# BCM_ECU.net
KiCad netlist of a schematic drawn in Altium Designer
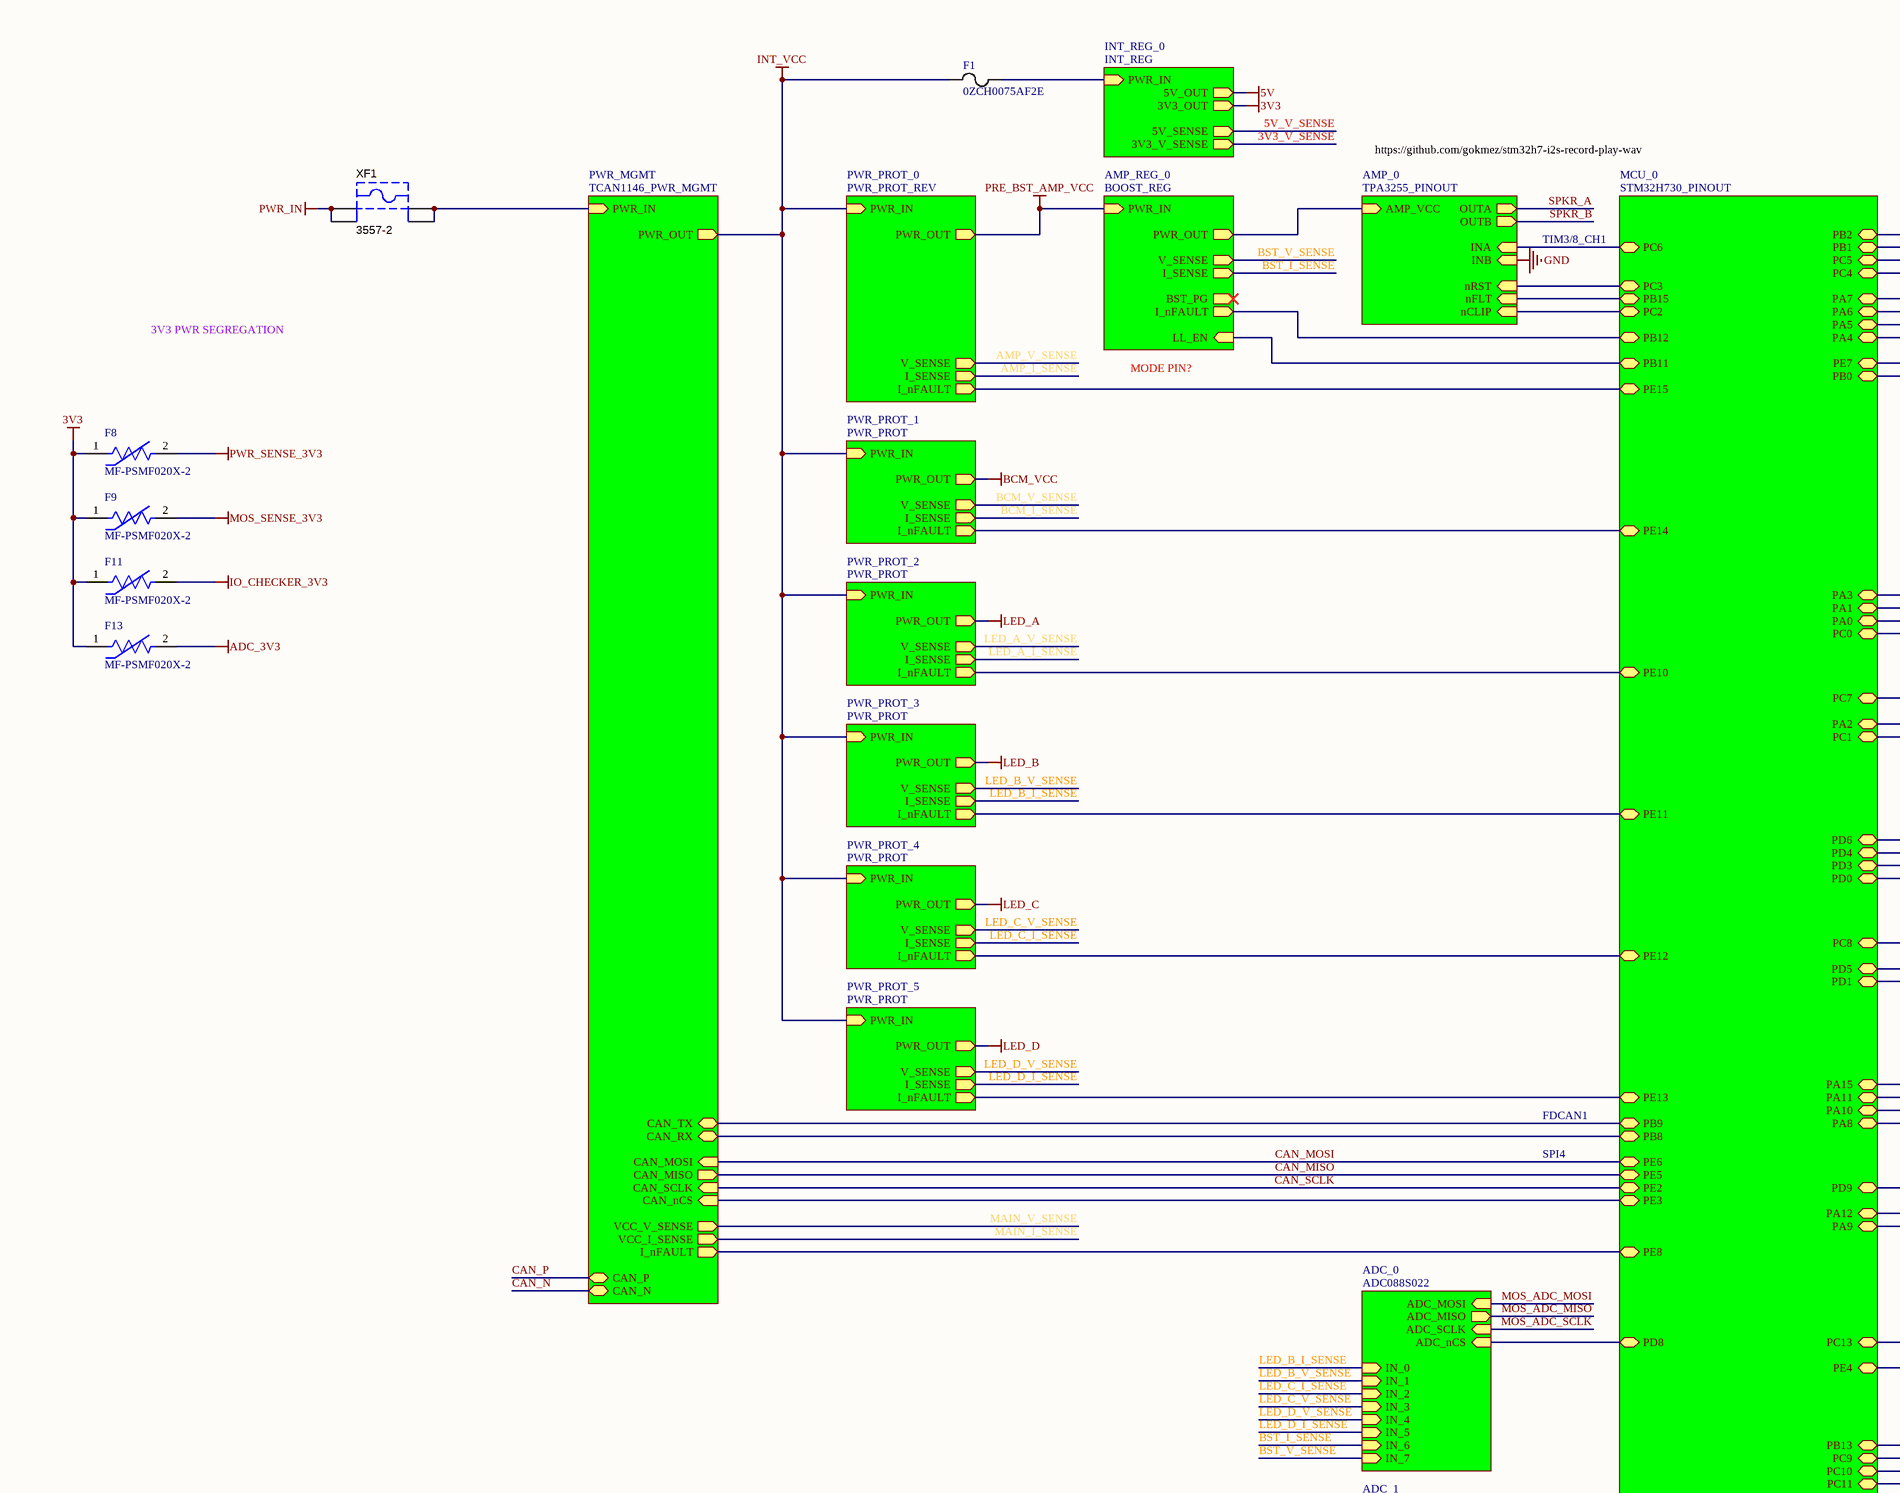
[diagram p0: BCM_ECU.SchDoc, top left]
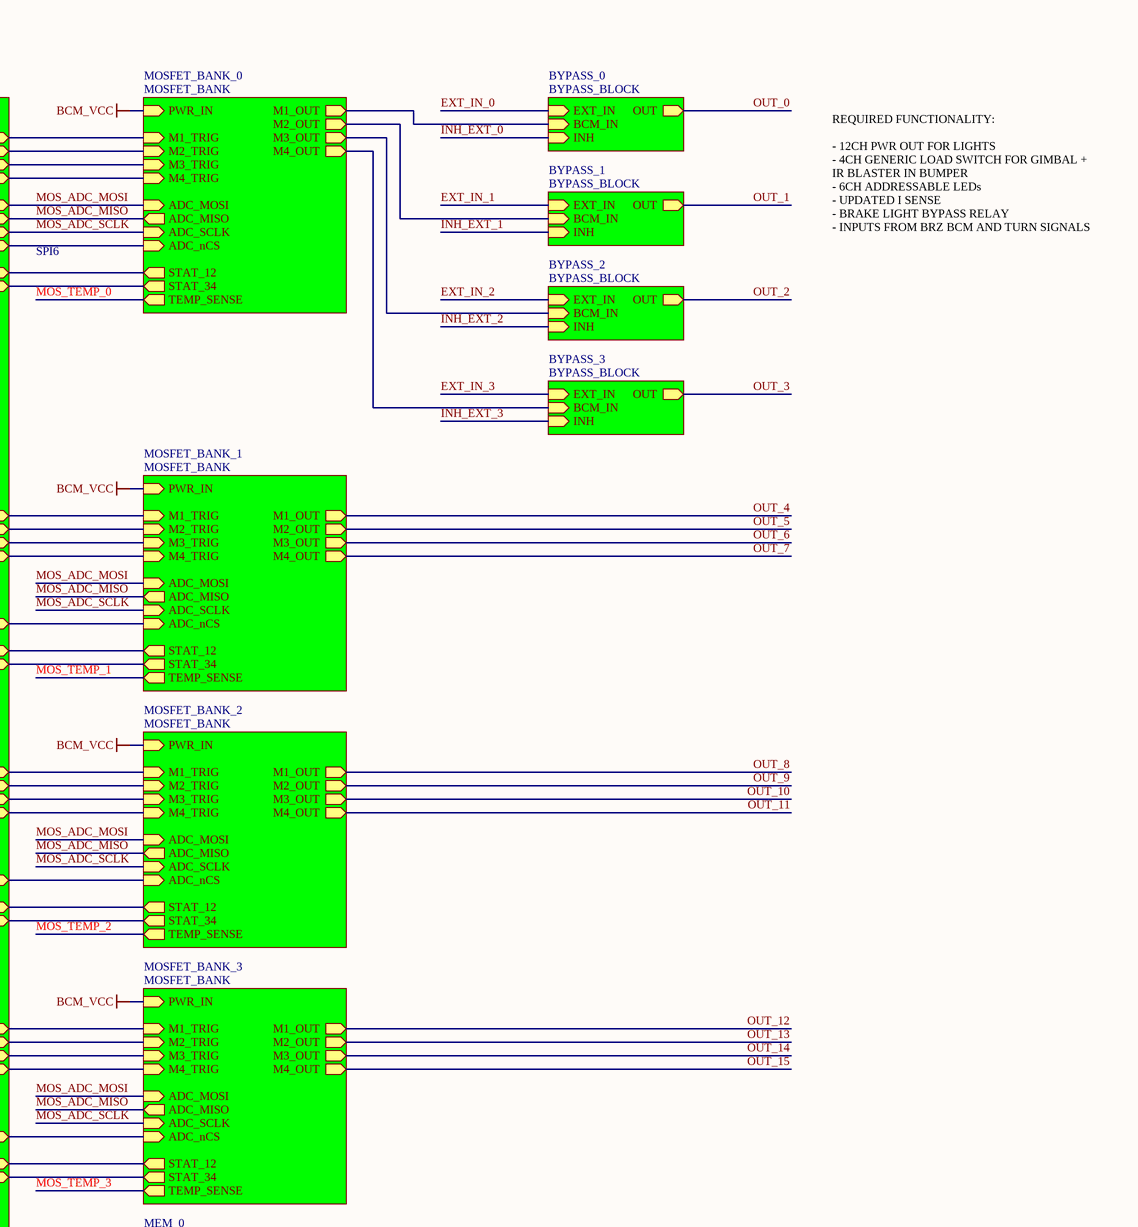
[diagram p1: BCM_ECU.SchDoc, top right]
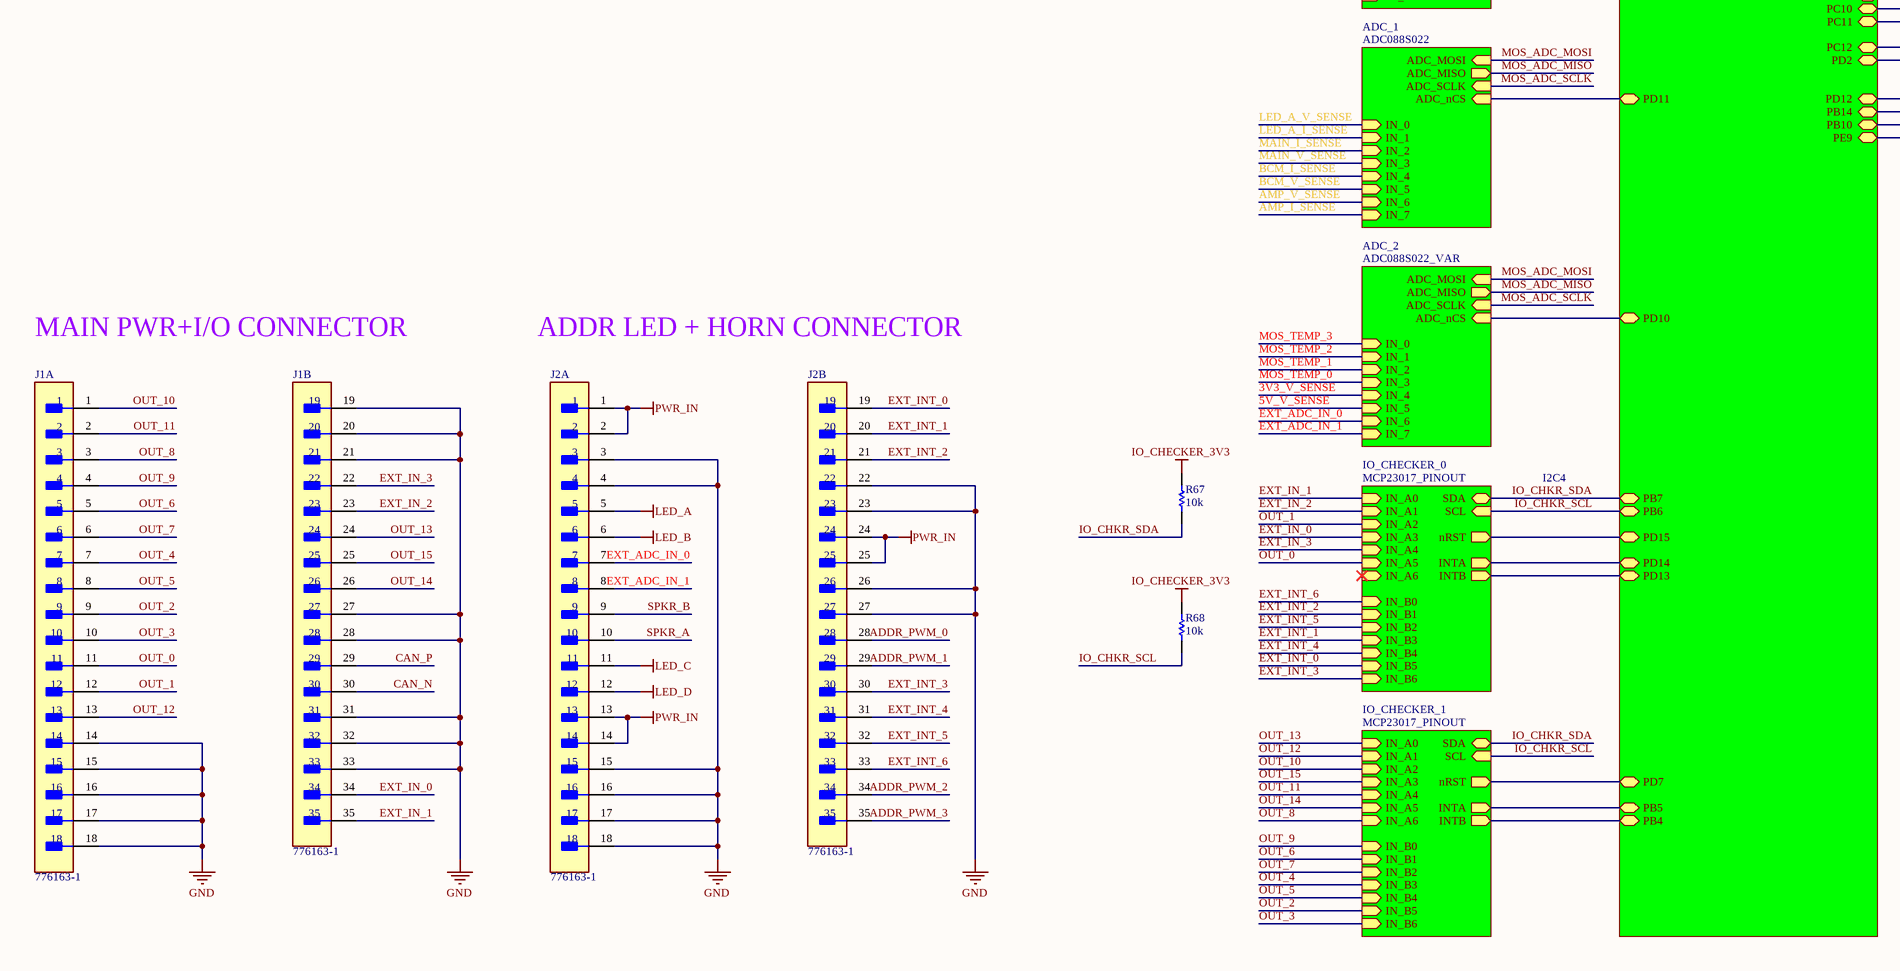
[diagram p2: BCM_ECU.SchDoc, bottom left]
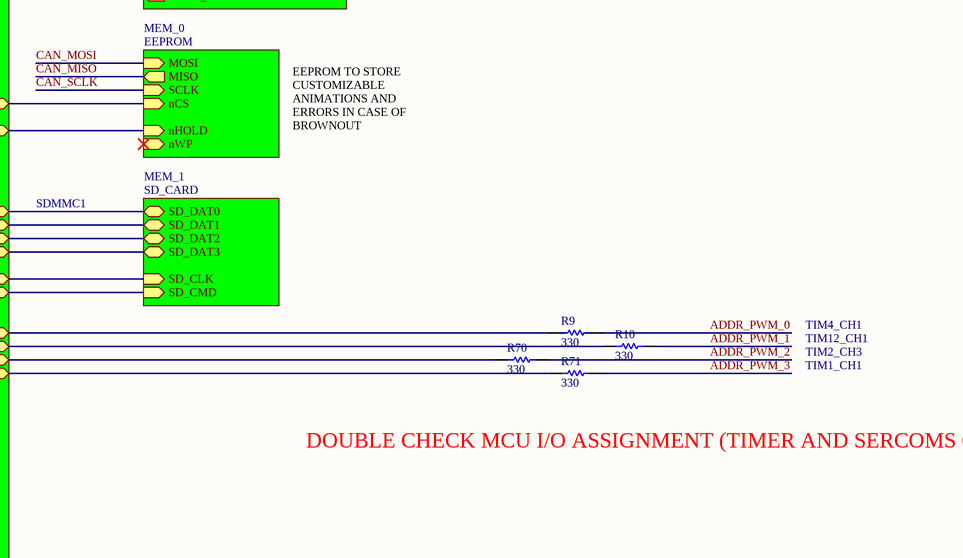
[diagram p3: BCM_ECU.SchDoc, bottom right]

(export (version "E")
  (design (tool "Eeschema 10.0.6"))
  (components
    (comp (ref "F1")
      (value "0ZCH0075AF2E")
      (footprint "0ZCH0075AF2E-Footprint-1")
      (description "PTC Thermistor")
      (libsource (lib "Space Concordia") (part "0ZCH0075AF2E"))
    )
    (comp (ref "F8")
      (value "MF-PSMF020X-2")
      (footprint "FP-MF-PSMF-MFG")
      (description "PTC RESET FUSE 9V 200MA 0805")
      (fields
        (field (name "MANUFACTURER") "Bourns")
        (field (name "OCTOPART") "https://octopart.com/mf-psmf020x-2-bourns-7483437")
      )
      (libsource (lib "Altium Content Vault") (part "3b148a6ebabc5fb4d708a66c052d352"))
    )
    (comp (ref "F9")
      (value "MF-PSMF020X-2")
      (footprint "FP-MF-PSMF-MFG")
      (description "PTC RESET FUSE 9V 200MA 0805")
      (fields
        (field (name "MANUFACTURER") "Bourns")
        (field (name "OCTOPART") "https://octopart.com/mf-psmf020x-2-bourns-7483437")
      )
      (libsource (lib "Altium Content Vault") (part "3b148a6ebabc5fb4d708a66c052d352"))
    )
    (comp (ref "F11")
      (value "MF-PSMF020X-2")
      (footprint "FP-MF-PSMF-MFG")
      (description "PTC RESET FUSE 9V 200MA 0805")
      (fields
        (field (name "MANUFACTURER") "Bourns")
        (field (name "OCTOPART") "https://octopart.com/mf-psmf020x-2-bourns-7483437")
      )
      (libsource (lib "Altium Content Vault") (part "3b148a6ebabc5fb4d708a66c052d352"))
    )
    (comp (ref "F13")
      (value "MF-PSMF020X-2")
      (footprint "FP-MF-PSMF-MFG")
      (description "PTC RESET FUSE 9V 200MA 0805")
      (fields
        (field (name "MANUFACTURER") "Bourns")
        (field (name "OCTOPART") "https://octopart.com/mf-psmf020x-2-bourns-7483437")
      )
      (libsource (lib "Altium Content Vault") (part "3b148a6ebabc5fb4d708a66c052d352"))
    )
    (comp (ref "J1")
      (value "776163-1")
      (footprint "FP-776163-1-MFG")
      (description "CONN HEADER R/A 35POS 4MM")
      (libsource (lib "Altium Content Vault") (part "519b18991870a11d3ebcd8ad3c0113e"))
    )
    (comp (ref "J2")
      (value "776163-1")
      (footprint "FP-776163-1-MFG")
      (description "CONN HEADER R/A 35POS 4MM")
      (libsource (lib "Altium Content Vault") (part "519b18991870a11d3ebcd8ad3c0113e"))
    )
    (comp (ref "R9")
      (value "330")
      (footprint "R0603B")
      (description "Resistor")
      (libsource (lib "Space Concordia") (part "Resistor"))
    )
    (comp (ref "R10")
      (value "330")
      (footprint "R0603B")
      (description "Resistor")
      (libsource (lib "Space Concordia") (part "Resistor"))
    )
    (comp (ref "R67")
      (value "10k")
      (footprint "R0603B")
      (description "Resistor")
      (libsource (lib "Space Concordia") (part "Resistor"))
    )
    (comp (ref "R68")
      (value "10k")
      (footprint "R0603B")
      (description "Resistor")
      (libsource (lib "Space Concordia") (part "Resistor"))
    )
    (comp (ref "R70")
      (value "330")
      (footprint "R0603B")
      (description "Resistor")
      (libsource (lib "Space Concordia") (part "Resistor"))
    )
    (comp (ref "R71")
      (value "330")
      (footprint "R0603B")
      (description "Resistor")
      (libsource (lib "Space Concordia") (part "Resistor"))
    )
    (comp (ref "XF1")
      (value "3557-2")
      (footprint "KSTN-3557-2")
      (description "FUSE HOLDER, PCB MOUNT, 500VAC, 20A, ROHS")
      (fields (field (name "VOLTAGE") "500V") (field (name "MANUFACTURER") "Keystone-Electronics"))
      (libsource (lib "Altium Content Vault") (part "FUSE_HOLDER-4"))
    )
  )
  (nets
    (net (code "10") (name "/ADDR_PWM_0") (class "Default")
      (node (ref "J2") (pin "28") (pinfunction "28_28") (pintype "passive"))
      (node (ref "R9") (pin "1") (pinfunction "1_1") (pintype "passive"))
    )
    (net (code "11") (name "/ADDR_PWM_1") (class "Default")
      (node (ref "J2") (pin "29") (pinfunction "29_29") (pintype "passive"))
      (node (ref "R10") (pin "1") (pinfunction "1_1") (pintype "passive"))
    )
    (net (code "12") (name "/ADDR_PWM_2") (class "Default")
      (node (ref "J2") (pin "34") (pinfunction "34_34") (pintype "passive"))
      (node (ref "R70") (pin "1") (pinfunction "1_1") (pintype "passive"))
    )
    (net (code "13") (name "/ADDR_PWM_3") (class "Default")
      (node (ref "J2") (pin "35") (pinfunction "35_35") (pintype "passive"))
      (node (ref "R71") (pin "1") (pinfunction "1_1") (pintype "passive"))
    )
    (net (code "23") (name "/CAN_N") (class "Default")
      (node (ref "J1") (pin "30") (pinfunction "30_30") (pintype "passive"))
    )
    (net (code "24") (name "/CAN_P") (class "Default")
      (node (ref "J1") (pin "29") (pinfunction "29_29") (pintype "passive"))
    )
    (net (code "29") (name "/EXT_ADC_IN_0") (class "Default")
      (node (ref "J2") (pin "7") (pinfunction "7_7") (pintype "passive"))
    )
    (net (code "30") (name "/EXT_ADC_IN_1") (class "Default")
      (node (ref "J2") (pin "8") (pinfunction "8_8") (pintype "passive"))
    )
    (net (code "31") (name "/EXT_INT_0") (class "Default")
      (node (ref "J2") (pin "19") (pinfunction "19_19") (pintype "passive"))
    )
    (net (code "32") (name "/EXT_INT_1") (class "Default")
      (node (ref "J2") (pin "20") (pinfunction "20_20") (pintype "passive"))
    )
    (net (code "33") (name "/EXT_INT_2") (class "Default")
      (node (ref "J2") (pin "21") (pinfunction "21_21") (pintype "passive"))
    )
    (net (code "34") (name "/EXT_INT_3") (class "Default")
      (node (ref "J2") (pin "30") (pinfunction "30_30") (pintype "passive"))
    )
    (net (code "35") (name "/EXT_INT_4") (class "Default")
      (node (ref "J2") (pin "31") (pinfunction "31_31") (pintype "passive"))
    )
    (net (code "36") (name "/EXT_INT_5") (class "Default")
      (node (ref "J2") (pin "32") (pinfunction "32_32") (pintype "passive"))
    )
    (net (code "37") (name "/EXT_INT_6") (class "Default")
      (node (ref "J2") (pin "33") (pinfunction "33_33") (pintype "passive"))
    )
    (net (code "38") (name "/EXT_IN_0") (class "Default")
      (node (ref "J1") (pin "34") (pinfunction "34_34") (pintype "passive"))
    )
    (net (code "39") (name "/EXT_IN_1") (class "Default")
      (node (ref "J1") (pin "35") (pinfunction "35_35") (pintype "passive"))
    )
    (net (code "40") (name "/EXT_IN_2") (class "Default")
      (node (ref "J1") (pin "23") (pinfunction "23_23") (pintype "passive"))
    )
    (net (code "41") (name "/EXT_IN_3") (class "Default")
      (node (ref "J1") (pin "22") (pinfunction "22_22") (pintype "passive"))
    )
    (net (code "52") (name "/IO_CHKR_SCL") (class "Default")
      (node (ref "R68") (pin "1") (pinfunction "1_1") (pintype "passive"))
    )
    (net (code "53") (name "/IO_CHKR_SDA") (class "Default")
      (node (ref "R67") (pin "1") (pinfunction "1_1") (pintype "passive"))
    )
    (net (code "100") (name "/OUT_0") (class "Default")
      (node (ref "J1") (pin "11") (pinfunction "11_11") (pintype "passive"))
    )
    (net (code "101") (name "/OUT_1") (class "Default")
      (node (ref "J1") (pin "12") (pinfunction "12_12") (pintype "passive"))
    )
    (net (code "102") (name "/OUT_2") (class "Default")
      (node (ref "J1") (pin "9") (pinfunction "9_9") (pintype "passive"))
    )
    (net (code "103") (name "/OUT_3") (class "Default")
      (node (ref "J1") (pin "10") (pinfunction "10_10") (pintype "passive"))
    )
    (net (code "104") (name "/OUT_4") (class "Default")
      (node (ref "J1") (pin "7") (pinfunction "7_7") (pintype "passive"))
    )
    (net (code "105") (name "/OUT_5") (class "Default")
      (node (ref "J1") (pin "8") (pinfunction "8_8") (pintype "passive"))
    )
    (net (code "106") (name "/OUT_6") (class "Default")
      (node (ref "J1") (pin "5") (pinfunction "5_5") (pintype "passive"))
    )
    (net (code "107") (name "/OUT_7") (class "Default")
      (node (ref "J1") (pin "6") (pinfunction "6_6") (pintype "passive"))
    )
    (net (code "108") (name "/OUT_8") (class "Default")
      (node (ref "J1") (pin "3") (pinfunction "3_3") (pintype "passive"))
    )
    (net (code "109") (name "/OUT_9") (class "Default")
      (node (ref "J1") (pin "4") (pinfunction "4_4") (pintype "passive"))
    )
    (net (code "110") (name "/OUT_10") (class "Default")
      (node (ref "J1") (pin "1") (pinfunction "1_1") (pintype "passive"))
    )
    (net (code "111") (name "/OUT_11") (class "Default")
      (node (ref "J1") (pin "2") (pinfunction "2_2") (pintype "passive"))
    )
    (net (code "112") (name "/OUT_12") (class "Default")
      (node (ref "J1") (pin "13") (pinfunction "13_13") (pintype "passive"))
    )
    (net (code "113") (name "/OUT_13") (class "Default")
      (node (ref "J1") (pin "24") (pinfunction "24_24") (pintype "passive"))
    )
    (net (code "114") (name "/OUT_14") (class "Default")
      (node (ref "J1") (pin "26") (pinfunction "26_26") (pintype "passive"))
    )
    (net (code "115") (name "/OUT_15") (class "Default")
      (node (ref "J1") (pin "25") (pinfunction "25_25") (pintype "passive"))
    )
    (net (code "116") (name "/PB10") (class "Default")
      (node (ref "R70") (pin "2") (pinfunction "2_2") (pintype "passive"))
    )
    (net (code "118") (name "/PB14") (class "Default")
      (node (ref "R10") (pin "2") (pinfunction "2_2") (pintype "passive"))
    )
    (net (code "128") (name "/PD12") (class "Default")
      (node (ref "R9") (pin "2") (pinfunction "2_2") (pintype "passive"))
    )
    (net (code "130") (name "/PE9") (class "Default")
      (node (ref "R71") (pin "2") (pinfunction "2_2") (pintype "passive"))
    )
    (net (code "131") (name "/PWR_IN") (class "Default")
      (node (ref "F1") (pin "2") (pinfunction "2_2") (pintype "passive"))
    )
    (net (code "132") (name "/PWR_IN_1") (class "Default")
      (node (ref "XF1") (pin "3") (pinfunction "3_3") (pintype "passive"))
      (node (ref "XF1") (pin "4") (pinfunction "4_4") (pintype "passive"))
    )
    (net (code "134") (name "/SPKR_A") (class "Default")
      (node (ref "J2") (pin "10") (pinfunction "10_10") (pintype "passive"))
    )
    (net (code "135") (name "/SPKR_B") (class "Default")
      (node (ref "J2") (pin "9") (pinfunction "9_9") (pintype "passive"))
    )
    (net (code "147") (name "3V3") (class "Default")
      (node (ref "F11") (pin "1") (pinfunction "1_1") (pintype "passive"))
      (node (ref "F13") (pin "1") (pinfunction "1_1") (pintype "passive"))
      (node (ref "F8") (pin "1") (pinfunction "1_1") (pintype "passive"))
      (node (ref "F9") (pin "1") (pinfunction "1_1") (pintype "passive"))
    )
    (net (code "149") (name "ADC_3V3") (class "Default")
      (node (ref "F13") (pin "2") (pinfunction "2_2") (pintype "passive"))
    )
    (net (code "151") (name "GND") (class "Default")
      (node (ref "J1") (pin "14") (pinfunction "14_14") (pintype "passive"))
      (node (ref "J1") (pin "15") (pinfunction "15_15") (pintype "passive"))
      (node (ref "J1") (pin "16") (pinfunction "16_16") (pintype "passive"))
      (node (ref "J1") (pin "17") (pinfunction "17_17") (pintype "passive"))
      (node (ref "J1") (pin "18") (pinfunction "18_18") (pintype "passive"))
      (node (ref "J1") (pin "19") (pinfunction "19_19") (pintype "passive"))
      (node (ref "J1") (pin "20") (pinfunction "20_20") (pintype "passive"))
      (node (ref "J1") (pin "21") (pinfunction "21_21") (pintype "passive"))
      (node (ref "J1") (pin "27") (pinfunction "27_27") (pintype "passive"))
      (node (ref "J1") (pin "28") (pinfunction "28_28") (pintype "passive"))
      (node (ref "J1") (pin "31") (pinfunction "31_31") (pintype "passive"))
      (node (ref "J1") (pin "32") (pinfunction "32_32") (pintype "passive"))
      (node (ref "J1") (pin "33") (pinfunction "33_33") (pintype "passive"))
      (node (ref "J2") (pin "15") (pinfunction "15_15") (pintype "passive"))
      (node (ref "J2") (pin "16") (pinfunction "16_16") (pintype "passive"))
      (node (ref "J2") (pin "17") (pinfunction "17_17") (pintype "passive"))
      (node (ref "J2") (pin "18") (pinfunction "18_18") (pintype "passive"))
      (node (ref "J2") (pin "22") (pinfunction "22_22") (pintype "passive"))
      (node (ref "J2") (pin "23") (pinfunction "23_23") (pintype "passive"))
      (node (ref "J2") (pin "26") (pinfunction "26_26") (pintype "passive"))
      (node (ref "J2") (pin "27") (pinfunction "27_27") (pintype "passive"))
      (node (ref "J2") (pin "3") (pinfunction "3_3") (pintype "passive"))
      (node (ref "J2") (pin "4") (pinfunction "4_4") (pintype "passive"))
    )
    (net (code "152") (name "INT_VCC") (class "Default")
      (node (ref "F1") (pin "1") (pinfunction "1_1") (pintype "passive"))
    )
    (net (code "153") (name "IO_CHECKER_3V3") (class "Default")
      (node (ref "F11") (pin "2") (pinfunction "2_2") (pintype "passive"))
      (node (ref "R67") (pin "2") (pinfunction "2_2") (pintype "passive"))
      (node (ref "R68") (pin "2") (pinfunction "2_2") (pintype "passive"))
    )
    (net (code "154") (name "LED_A") (class "Default")
      (node (ref "J2") (pin "5") (pinfunction "5_5") (pintype "passive"))
    )
    (net (code "155") (name "LED_B") (class "Default")
      (node (ref "J2") (pin "6") (pinfunction "6_6") (pintype "passive"))
    )
    (net (code "156") (name "LED_C") (class "Default")
      (node (ref "J2") (pin "11") (pinfunction "11_11") (pintype "passive"))
    )
    (net (code "157") (name "LED_D") (class "Default")
      (node (ref "J2") (pin "12") (pinfunction "12_12") (pintype "passive"))
    )
    (net (code "158") (name "MOS_SENSE_3V3") (class "Default")
      (node (ref "F9") (pin "2") (pinfunction "2_2") (pintype "passive"))
    )
    (net (code "160") (name "PWR_IN") (class "Default")
      (node (ref "J2") (pin "1") (pinfunction "1_1") (pintype "passive"))
      (node (ref "J2") (pin "13") (pinfunction "13_13") (pintype "passive"))
      (node (ref "J2") (pin "14") (pinfunction "14_14") (pintype "passive"))
      (node (ref "J2") (pin "2") (pinfunction "2_2") (pintype "passive"))
      (node (ref "J2") (pin "24") (pinfunction "24_24") (pintype "passive"))
      (node (ref "J2") (pin "25") (pinfunction "25_25") (pintype "passive"))
      (node (ref "XF1") (pin "1") (pinfunction "1_1") (pintype "passive"))
      (node (ref "XF1") (pin "2") (pinfunction "2_2") (pintype "passive"))
    )
    (net (code "161") (name "PWR_SENSE_3V3") (class "Default")
      (node (ref "F8") (pin "2") (pinfunction "2_2") (pintype "passive"))
    )
  )
)
